# DM3370_LCD_LEDring.net
KiCad netlist of a schematic drawn in Altium Designer
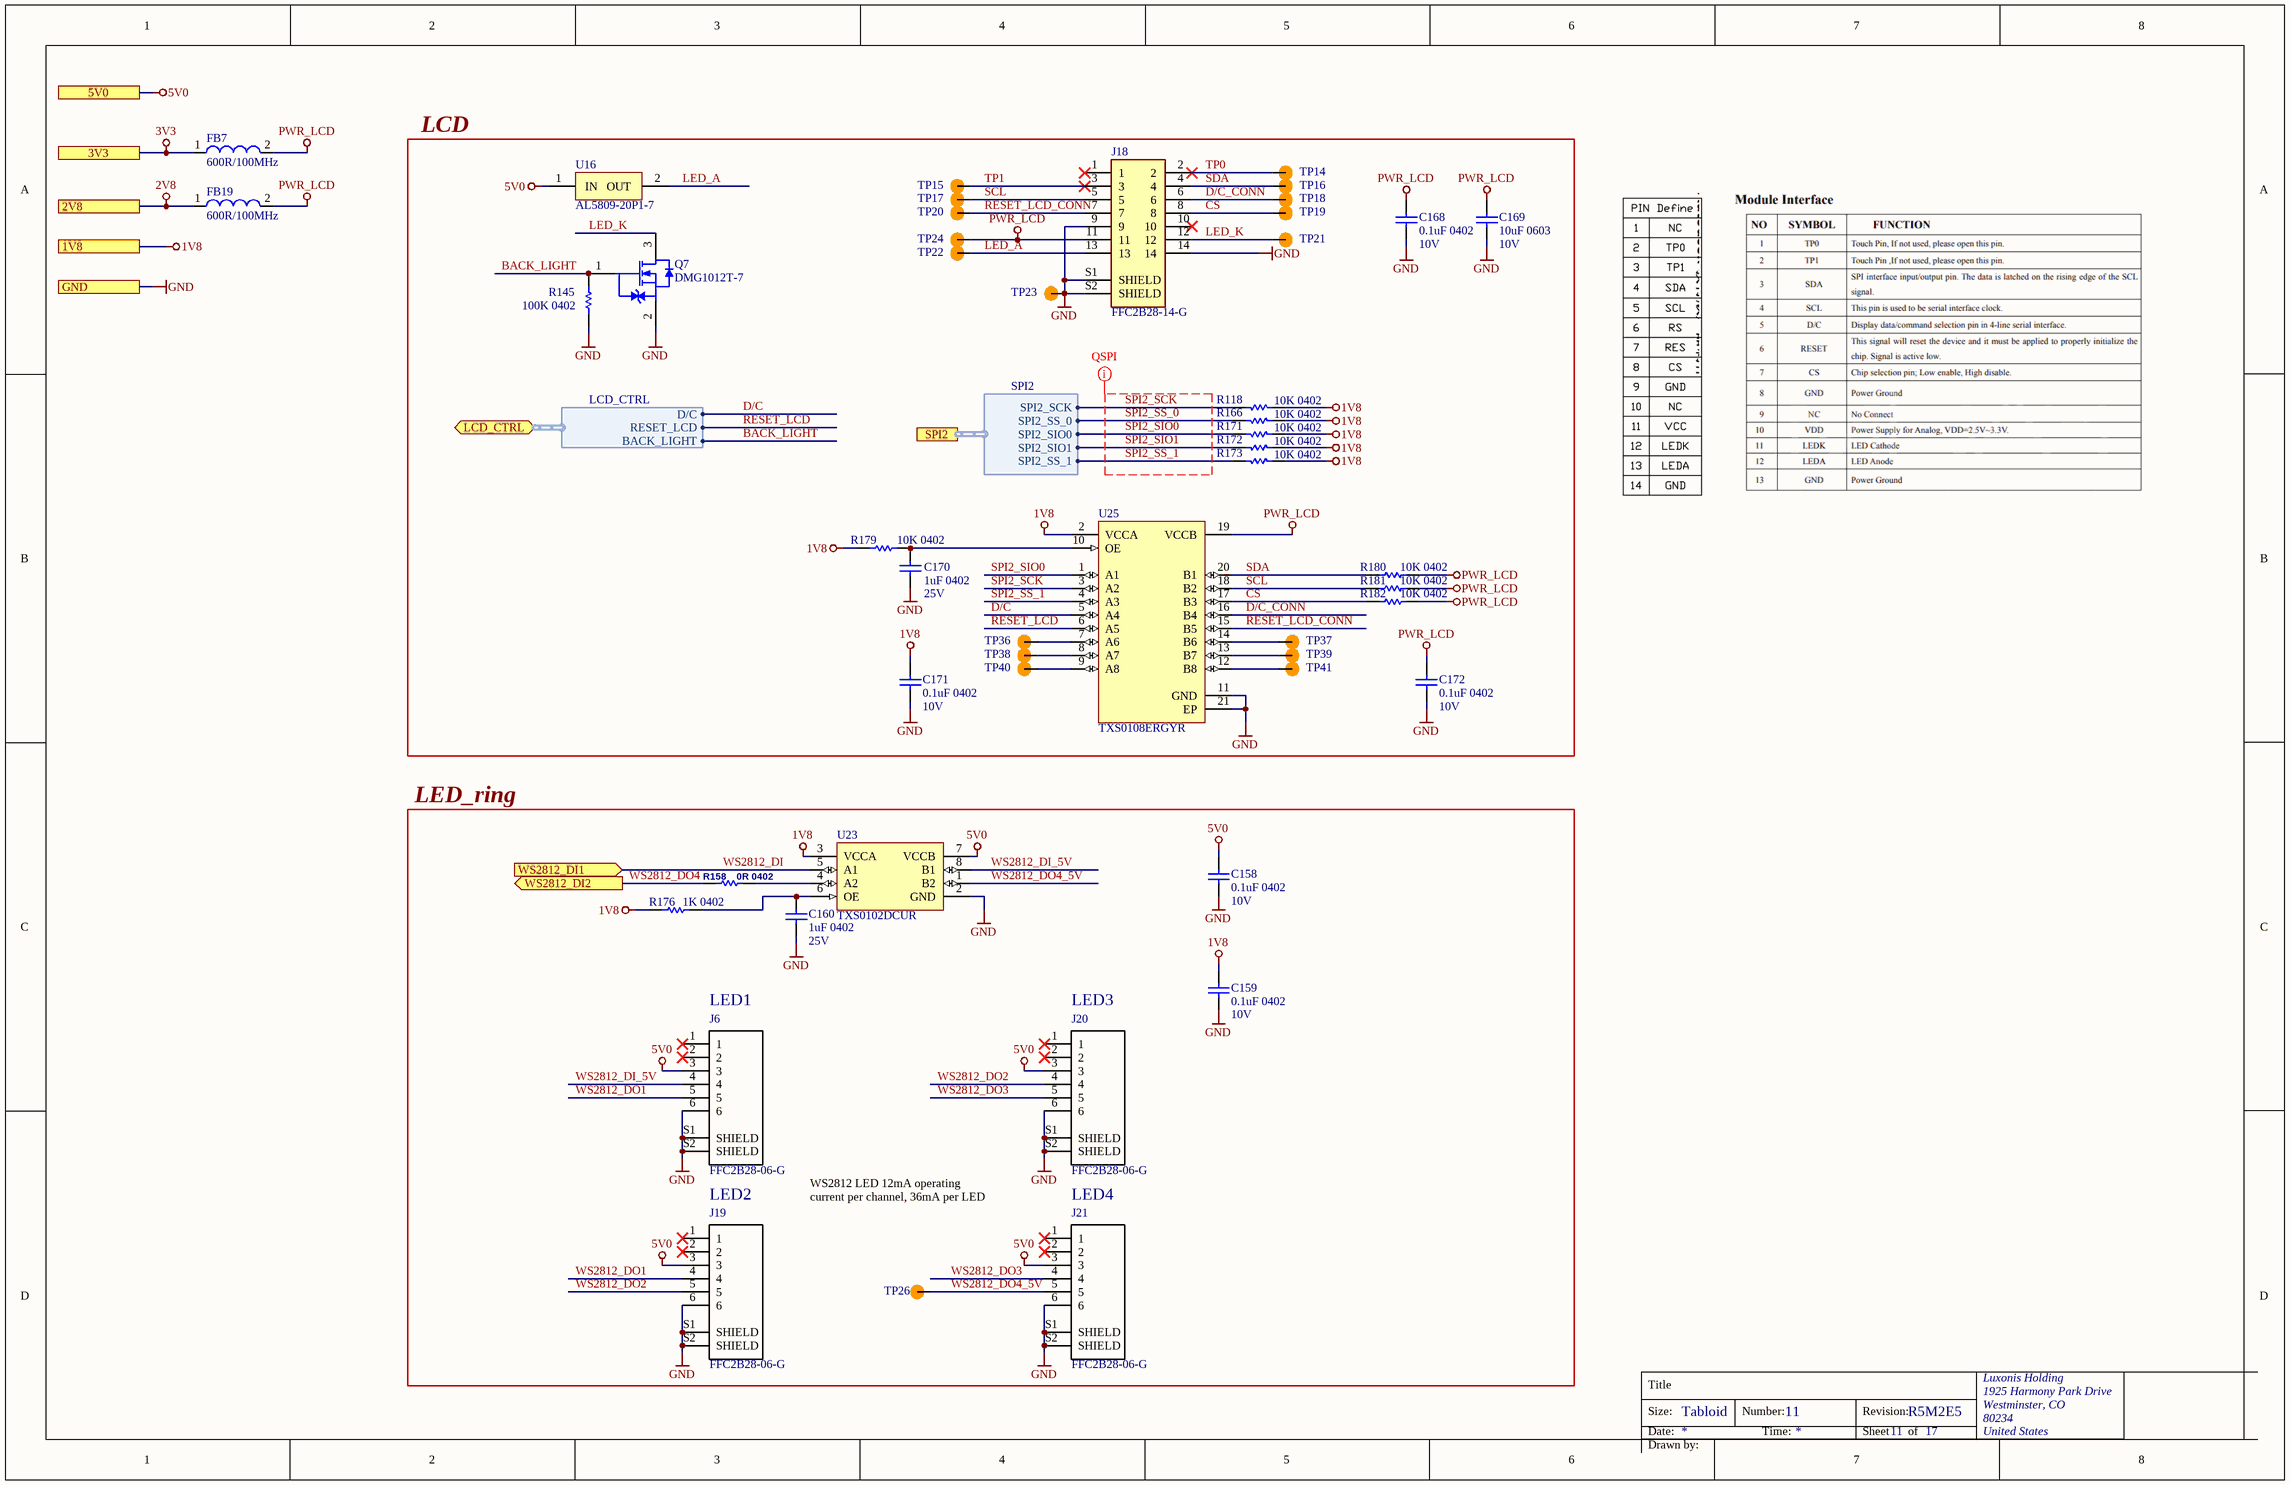
[diagram p0: DM3370_LCD_LEDring.SchDoc]

(export (version "E")
  (design (tool "Eeschema 10.0.6"))
  (components
    (comp (ref "C158")
      (value "0.1uF 0402")
      (footprint "CAP_Altium_Vault_Generic:CAPC0402(1005)70_L")
      (description "CAP CER 0.1UF 10V X7R 0402 5%")
      (fields (field (name "TOLERANCE") "5%") (field (name "VOLTAGE RATING") "10V"))
      (libsource (lib "LuxonisMaster") (part "GRM155R71A104JA01D"))
    )
    (comp (ref "C159")
      (value "0.1uF 0402")
      (footprint "CAP_Altium_Vault_Generic:CAPC0402(1005)70_L")
      (description "CAP CER 0.1UF 10V X7R 0402 5%")
      (fields (field (name "TOLERANCE") "5%") (field (name "VOLTAGE RATING") "10V"))
      (libsource (lib "LuxonisMaster") (part "GRM155R71A104JA01D"))
    )
    (comp (ref "C160")
      (value "1uF 0402")
      (footprint "CAP_Altium_Vault_Generic:CAPC0402(1005)70_L")
      (description "CAP CER 1UF 25V X5R 0402 10%")
      (fields
        (field (name "TOLERANCE") "10%")
        (field (name "VOLTAGE") "25V")
        (field (name "VOLTAGE RATING") "25V")
      )
      (libsource (lib "LuxonisMaster") (part "GRM155R61E105KA12D"))
    )
    (comp (ref "C168")
      (value "0.1uF 0402")
      (footprint "CAP_Altium_Vault_Generic:CAPC0402(1005)70_L")
      (description "CAP CER 0.1UF 10V X7R 0402 5%")
      (fields (field (name "TOLERANCE") "5%") (field (name "VOLTAGE RATING") "10V"))
      (libsource (lib "LuxonisMaster") (part "GRM155R71A104JA01D"))
    )
    (comp (ref "C169")
      (value "10uF 0603")
      (footprint "CAP_Altium_Vault_Generic:CAPC0603(1608)100_L")
      (description "CAP CER 10UF 10V X5R 0603 20%")
      (fields (field (name "TOLERANCE") "20%") (field (name "VOLTAGE RATING") "10V"))
      (libsource (lib "LuxonisMaster") (part "GRM188R61A106ME69D"))
    )
    (comp (ref "C170")
      (value "1uF 0402")
      (footprint "CAP_Altium_Vault_Generic:CAPC0402(1005)70_L")
      (description "CAP CER 1UF 25V X5R 0402 10%")
      (fields
        (field (name "TOLERANCE") "10%")
        (field (name "VOLTAGE") "25V")
        (field (name "VOLTAGE RATING") "25V")
      )
      (libsource (lib "LuxonisMaster") (part "GRM155R61E105KA12D"))
    )
    (comp (ref "C171")
      (value "0.1uF 0402")
      (footprint "CAP_Altium_Vault_Generic:CAPC0402(1005)70_L")
      (description "CAP CER 0.1UF 10V X7R 0402 5%")
      (fields (field (name "TOLERANCE") "5%") (field (name "VOLTAGE RATING") "10V"))
      (libsource (lib "LuxonisMaster") (part "GRM155R71A104JA01D"))
    )
    (comp (ref "C172")
      (value "0.1uF 0402")
      (footprint "CAP_Altium_Vault_Generic:CAPC0402(1005)70_L")
      (description "CAP CER 0.1UF 10V X7R 0402 5%")
      (fields (field (name "TOLERANCE") "5%") (field (name "VOLTAGE RATING") "10V"))
      (libsource (lib "LuxonisMaster") (part "GRM155R71A104JA01D"))
    )
    (comp (ref "FB7")
      (value "600R/100MHz")
      (footprint "LuxonisMaster:2508056017Y2")
      (description "FERRITE BEAD, 0.1OHM, 2A, 0805, 600R/100MHz")
      (fields (field (name "TOLERANCE") "25%"))
      (libsource (lib "LuxonisMaster") (part "2508056017Y2"))
    )
    (comp (ref "FB19")
      (value "600R/100MHz")
      (footprint "LuxonisMaster:2508056017Y2")
      (description "FERRITE BEAD, 0.1OHM, 2A, 0805, 600R/100MHz")
      (fields (field (name "TOLERANCE") "25%"))
      (libsource (lib "LuxonisMaster") (part "2508056017Y2"))
    )
    (comp (ref "J6")
      (value "FFC2B28-06-G")
      (footprint "FFC2B28-06-G")
      (description "Connector, Ffc, R/a Rcpt, 6POS, 1ROW, 0.5MM;")
      (libsource (lib "Luxonis LLC") (part "FFC2B28-06-G"))
    )
    (comp (ref "J18")
      (value "FFC2B28-14-G")
      (footprint "GCT_FFC2B28-14-G")
      (description "14W, 0.5mm FFC Con, R/A, Dual Cont, B/Flp, H1.0mm, Gld, SMT, T&R")
      (libsource (lib "Luxonis LLC") (part "FFC2B28-14-G"))
    )
    (comp (ref "J19")
      (value "FFC2B28-06-G")
      (footprint "FFC2B28-06-G")
      (description "Connector, Ffc, R/a Rcpt, 6POS, 1ROW, 0.5MM;")
      (libsource (lib "Luxonis LLC") (part "FFC2B28-06-G"))
    )
    (comp (ref "J20")
      (value "FFC2B28-06-G")
      (footprint "FFC2B28-06-G")
      (description "Connector, Ffc, R/a Rcpt, 6POS, 1ROW, 0.5MM;")
      (libsource (lib "Luxonis LLC") (part "FFC2B28-06-G"))
    )
    (comp (ref "J21")
      (value "FFC2B28-06-G")
      (footprint "FFC2B28-06-G")
      (description "Connector, Ffc, R/a Rcpt, 6POS, 1ROW, 0.5MM;")
      (libsource (lib "Luxonis LLC") (part "FFC2B28-06-G"))
    )
    (comp (ref "Q7")
      (value "DMG1012T-7")
      (footprint "DMG1012T-7")
      (description "MOSFET N-CH 20V 630MA SOT-523")
      (libsource (lib "Luxonis LLC") (part "DMG1012T-7"))
    )
    (comp (ref "R118")
      (value "10K 0402")
      (footprint "RES_Altium_Vault_Generic:RESC0402(1005)_L")
      (fields (field (name "TOLERANCE") "1%"))
      (libsource (lib "LuxonisMaster") (part "RC0402FR-1310KL"))
    )
    (comp (ref "R145")
      (value "100K 0402")
      (footprint "RES_Altium_Vault_Generic:RESC0402(1005)_L")
      (description "RES SMD 100K OHM 1% 1/16W 0402")
      (fields (field (name "TOLERANCE") "1%"))
      (libsource (lib "LuxonisMaster") (part "RC0402FR-07100KL"))
    )
    (comp (ref "R158")
      (value "0R 0402")
      (footprint "RES_Altium_Vault_Generic:RESC0402(1005)_L")
      (description "RES SMD 0 OHM JUMPER 1/16W 0402")
      (fields (field (name "TOLERANCE") "5%"))
      (libsource (lib "LuxonisMaster") (part "CRCW04020000Z0ED"))
    )
    (comp (ref "R166")
      (value "10K 0402")
      (footprint "RES_Altium_Vault_Generic:RESC0402(1005)_L")
      (fields (field (name "TOLERANCE") "1%"))
      (libsource (lib "LuxonisMaster") (part "RC0402FR-1310KL"))
    )
    (comp (ref "R171")
      (value "10K 0402")
      (footprint "RES_Altium_Vault_Generic:RESC0402(1005)_L")
      (fields (field (name "TOLERANCE") "1%"))
      (libsource (lib "LuxonisMaster") (part "RC0402FR-1310KL"))
    )
    (comp (ref "R172")
      (value "10K 0402")
      (footprint "RES_Altium_Vault_Generic:RESC0402(1005)_L")
      (fields (field (name "TOLERANCE") "1%"))
      (libsource (lib "LuxonisMaster") (part "RC0402FR-1310KL"))
    )
    (comp (ref "R173")
      (value "10K 0402")
      (footprint "RES_Altium_Vault_Generic:RESC0402(1005)_L")
      (fields (field (name "TOLERANCE") "1%"))
      (libsource (lib "LuxonisMaster") (part "RC0402FR-1310KL"))
    )
    (comp (ref "R176")
      (value "1K 0402")
      (footprint "RES_Altium_Vault_Generic:RESC0402(1005)_L")
      (fields (field (name "TOLERANCE") "1%"))
      (libsource (lib "LuxonisMaster") (part "RC0402FR-071KL"))
    )
    (comp (ref "R179")
      (value "10K 0402")
      (footprint "RES_Altium_Vault_Generic:RESC0402(1005)_L")
      (fields (field (name "TOLERANCE") "1%"))
      (libsource (lib "LuxonisMaster") (part "RC0402FR-1310KL"))
    )
    (comp (ref "R180")
      (value "10K 0402")
      (footprint "RES_Altium_Vault_Generic:RESC0402(1005)_L")
      (fields (field (name "TOLERANCE") "1%"))
      (libsource (lib "LuxonisMaster") (part "RC0402FR-1310KL"))
    )
    (comp (ref "R181")
      (value "10K 0402")
      (footprint "RES_Altium_Vault_Generic:RESC0402(1005)_L")
      (fields (field (name "TOLERANCE") "1%"))
      (libsource (lib "LuxonisMaster") (part "RC0402FR-1310KL"))
    )
    (comp (ref "R182")
      (value "10K 0402")
      (footprint "RES_Altium_Vault_Generic:RESC0402(1005)_L")
      (fields (field (name "TOLERANCE") "1%"))
      (libsource (lib "LuxonisMaster") (part "RC0402FR-1310KL"))
    )
    (comp (ref "TP14")
      (value "TEST_POINT")
      (footprint "TP075_150_NS")
      (libsource (lib "Luxonis LLC") (part "TEST_POINT"))
    )
    (comp (ref "TP15")
      (value "TEST_POINT")
      (footprint "TP075_150_NS")
      (libsource (lib "Luxonis LLC") (part "TEST_POINT"))
    )
    (comp (ref "TP16")
      (value "TEST_POINT")
      (footprint "TP075_150_NS")
      (libsource (lib "Luxonis LLC") (part "TEST_POINT"))
    )
    (comp (ref "TP17")
      (value "TEST_POINT")
      (footprint "TP075_150_NS")
      (libsource (lib "Luxonis LLC") (part "TEST_POINT"))
    )
    (comp (ref "TP18")
      (value "TEST_POINT")
      (footprint "TP075_150_NS")
      (libsource (lib "Luxonis LLC") (part "TEST_POINT"))
    )
    (comp (ref "TP19")
      (value "TEST_POINT")
      (footprint "TP075_150_NS")
      (libsource (lib "Luxonis LLC") (part "TEST_POINT"))
    )
    (comp (ref "TP20")
      (value "TEST_POINT")
      (footprint "TP075_150_NS")
      (libsource (lib "Luxonis LLC") (part "TEST_POINT"))
    )
    (comp (ref "TP21")
      (value "TEST_POINT")
      (footprint "TP075_150_NS")
      (libsource (lib "Luxonis LLC") (part "TEST_POINT"))
    )
    (comp (ref "TP22")
      (value "TEST_POINT")
      (footprint "TP075_150_NS")
      (libsource (lib "Luxonis LLC") (part "TEST_POINT"))
    )
    (comp (ref "TP23")
      (value "TEST_POINT")
      (footprint "TP075_150_NS")
      (libsource (lib "Luxonis LLC") (part "TEST_POINT"))
    )
    (comp (ref "TP24")
      (value "TEST_POINT")
      (footprint "TP075_150_NS")
      (libsource (lib "Luxonis LLC") (part "TEST_POINT"))
    )
    (comp (ref "TP26")
      (value "TEST_POINT")
      (footprint "TP075_150_NS")
      (libsource (lib "Luxonis LLC") (part "TEST_POINT"))
    )
    (comp (ref "TP36")
      (value "TEST_POINT")
      (footprint "TP075_150_NS")
      (libsource (lib "Luxonis LLC") (part "TEST_POINT"))
    )
    (comp (ref "TP37")
      (value "TEST_POINT")
      (footprint "TP075_150_NS")
      (libsource (lib "Luxonis LLC") (part "TEST_POINT"))
    )
    (comp (ref "TP38")
      (value "TEST_POINT")
      (footprint "TP075_150_NS")
      (libsource (lib "Luxonis LLC") (part "TEST_POINT"))
    )
    (comp (ref "TP39")
      (value "TEST_POINT")
      (footprint "TP075_150_NS")
      (libsource (lib "Luxonis LLC") (part "TEST_POINT"))
    )
    (comp (ref "TP40")
      (value "TEST_POINT")
      (footprint "TP075_150_NS")
      (libsource (lib "Luxonis LLC") (part "TEST_POINT"))
    )
    (comp (ref "TP41")
      (value "TEST_POINT")
      (footprint "TP075_150_NS")
      (libsource (lib "Luxonis LLC") (part "TEST_POINT"))
    )
    (comp (ref "U16")
      (value "AL5809-20P1-7")
      (footprint "DIOD-POWERDI123-2_B_V")
      (description "Two Terminal Constant Current LED Driver PowerDI, 2.5V to 60V, -40 °C to 125 °C")
      (libsource (lib "Luxonis LLC") (part "DIOD-AL5809-2"))
    )
    (comp (ref "U23")
      (value "TXS0102DCUR")
      (footprint "TXS0102DCUR")
      (description "TEXAS INSTRUMENTS - TXS0102DCUR - IC, TRANSLATOR, 2 BIT, BI, US-8")
      (libsource (lib "Luxonis LLC") (part "TXS0102DCUR"))
    )
    (comp (ref "U25")
      (value "TXS0108ERGYR")
      (footprint "TXS0108ERGYR")
      (description "IC TRNSLTR BIDIRECTIONAL 20VQFN")
      (libsource (lib "Luxonis LLC") (part "TXS0108ERGYR"))
    )
  )
  (nets
    (net (code "3") (name "/BACK_LIGHT") (class "Default")
      (node (ref "Q7") (pin "1") (pinfunction "1_1") (pintype "passive"))
      (node (ref "R145") (pin "2") (pinfunction "2_2") (pintype "passive"))
    )
    (net (code "4") (name "/CS") (class "Default")
      (node (ref "J18") (pin "8") (pinfunction "8_8") (pintype "passive"))
      (node (ref "R182") (pin "1") (pinfunction "1_1") (pintype "passive"))
      (node (ref "TP19") (pin "1") (pintype "passive"))
      (node (ref "U25") (pin "17") (pinfunction "B3_17") (pintype "bidirectional"))
    )
    (net (code "5") (name "/D{slash}C") (class "Default")
      (node (ref "U25") (pin "5") (pinfunction "A4_5") (pintype "bidirectional"))
    )
    (net (code "6") (name "/D{slash}C_CONN") (class "Default")
      (node (ref "J18") (pin "6") (pinfunction "6_6") (pintype "passive"))
      (node (ref "TP18") (pin "1") (pintype "passive"))
      (node (ref "U25") (pin "16") (pinfunction "B4_16") (pintype "bidirectional"))
    )
    (net (code "7") (name "/LED_A") (class "Default")
      (node (ref "J18") (pin "13") (pinfunction "13_13") (pintype "passive"))
      (node (ref "TP22") (pin "1") (pintype "passive"))
      (node (ref "U16") (pin "2") (pinfunction "OUT_2") (pintype "passive"))
    )
    (net (code "8") (name "/LED_K") (class "Default")
      (node (ref "J18") (pin "12") (pinfunction "12_12") (pintype "passive"))
      (node (ref "Q7") (pin "3") (pinfunction "3_3") (pintype "passive"))
      (node (ref "TP21") (pin "1") (pintype "passive"))
    )
    (net (code "9") (name "/RESET_LCD") (class "Default")
      (node (ref "U25") (pin "6") (pinfunction "A5_6") (pintype "bidirectional"))
    )
    (net (code "10") (name "/RESET_LCD_CONN") (class "Default")
      (node (ref "J18") (pin "7") (pinfunction "7_7") (pintype "passive"))
      (node (ref "TP20") (pin "1") (pintype "passive"))
      (node (ref "U25") (pin "15") (pinfunction "B5_15") (pintype "bidirectional"))
    )
    (net (code "11") (name "/SCL") (class "Default")
      (node (ref "J18") (pin "5") (pinfunction "5_5") (pintype "passive"))
      (node (ref "R181") (pin "1") (pinfunction "1_1") (pintype "passive"))
      (node (ref "TP17") (pin "1") (pintype "passive"))
      (node (ref "U25") (pin "18") (pinfunction "B2_18") (pintype "bidirectional"))
    )
    (net (code "12") (name "/SDA") (class "Default")
      (node (ref "J18") (pin "4") (pinfunction "4_4") (pintype "passive"))
      (node (ref "R180") (pin "1") (pinfunction "1_1") (pintype "passive"))
      (node (ref "TP16") (pin "1") (pintype "passive"))
      (node (ref "U25") (pin "20") (pinfunction "B1_20") (pintype "bidirectional"))
    )
    (net (code "13") (name "/SPI2_SCK") (class "Default")
      (node (ref "R118") (pin "2") (pinfunction "2_2") (pintype "passive"))
      (node (ref "U25") (pin "3") (pinfunction "A2_3") (pintype "bidirectional"))
    )
    (net (code "14") (name "/SPI2_SIO0") (class "Default")
      (node (ref "R171") (pin "2") (pinfunction "2_2") (pintype "passive"))
      (node (ref "U25") (pin "1") (pinfunction "A1_1") (pintype "bidirectional"))
    )
    (net (code "15") (name "/SPI2_SIO1") (class "Default")
      (node (ref "R172") (pin "2") (pinfunction "2_2") (pintype "passive"))
    )
    (net (code "16") (name "/SPI2_SS_0") (class "Default")
      (node (ref "R166") (pin "2") (pinfunction "2_2") (pintype "passive"))
    )
    (net (code "17") (name "/SPI2_SS_1") (class "Default")
      (node (ref "R173") (pin "2") (pinfunction "2_2") (pintype "passive"))
      (node (ref "U25") (pin "4") (pinfunction "A3_4") (pintype "bidirectional"))
    )
    (net (code "18") (name "/TP0") (class "Default")
      (node (ref "J18") (pin "2") (pinfunction "2_2") (pintype "passive"))
      (node (ref "TP14") (pin "1") (pintype "passive"))
    )
    (net (code "19") (name "/TP1") (class "Default")
      (node (ref "J18") (pin "3") (pinfunction "3_3") (pintype "passive"))
      (node (ref "TP15") (pin "1") (pintype "passive"))
    )
    (net (code "20") (name "/WS2812_DI") (class "Default")
      (node (ref "U23") (pin "5") (pinfunction "A1_5") (pintype "bidirectional"))
    )
    (net (code "21") (name "/WS2812_DI_5V") (class "Default")
      (node (ref "J6") (pin "4") (pinfunction "4_4") (pintype "passive"))
      (node (ref "U23") (pin "8") (pinfunction "B1_8") (pintype "bidirectional"))
    )
    (net (code "22") (name "/WS2812_DO1") (class "Default")
      (node (ref "J19") (pin "4") (pinfunction "4_4") (pintype "passive"))
      (node (ref "J6") (pin "5") (pinfunction "5_5") (pintype "passive"))
    )
    (net (code "23") (name "/WS2812_DO2") (class "Default")
      (node (ref "J19") (pin "5") (pinfunction "5_5") (pintype "passive"))
      (node (ref "J20") (pin "4") (pinfunction "4_4") (pintype "passive"))
    )
    (net (code "24") (name "/WS2812_DO3") (class "Default")
      (node (ref "J20") (pin "5") (pinfunction "5_5") (pintype "passive"))
      (node (ref "J21") (pin "4") (pinfunction "4_4") (pintype "passive"))
    )
    (net (code "25") (name "/WS2812_DO4") (class "Default")
      (node (ref "R158") (pin "2") (pinfunction "2_2") (pintype "passive"))
    )
    (net (code "26") (name "/WS2812_DO4_5V") (class "Default")
      (node (ref "J21") (pin "5") (pinfunction "5_5") (pintype "passive"))
      (node (ref "TP26") (pin "1") (pintype "passive"))
      (node (ref "U23") (pin "1") (pinfunction "B2_1") (pintype "bidirectional"))
    )
    (net (code "29") (name "1V8") (class "Default")
      (node (ref "C159") (pin "2") (pinfunction "2_2") (pintype "passive"))
      (node (ref "C171") (pin "2") (pinfunction "2_2") (pintype "passive"))
      (node (ref "R118") (pin "1") (pinfunction "1_1") (pintype "passive"))
      (node (ref "R166") (pin "1") (pinfunction "1_1") (pintype "passive"))
      (node (ref "R171") (pin "1") (pinfunction "1_1") (pintype "passive"))
      (node (ref "R172") (pin "1") (pinfunction "1_1") (pintype "passive"))
      (node (ref "R173") (pin "1") (pinfunction "1_1") (pintype "passive"))
      (node (ref "R176") (pin "2") (pinfunction "2_2") (pintype "passive"))
      (node (ref "R179") (pin "2") (pinfunction "2_2") (pintype "passive"))
      (node (ref "U23") (pin "3") (pinfunction "VCCA_3") (pintype "power_in"))
      (node (ref "U25") (pin "2") (pinfunction "VCCA_2") (pintype "power_in"))
    )
    (net (code "30") (name "2V8") (class "Default")
      (node (ref "FB19") (pin "1") (pinfunction "1_1") (pintype "passive"))
    )
    (net (code "31") (name "3V3") (class "Default")
      (node (ref "FB7") (pin "1") (pinfunction "1_1") (pintype "passive"))
    )
    (net (code "32") (name "5V0") (class "Default")
      (node (ref "C158") (pin "2") (pinfunction "2_2") (pintype "passive"))
      (node (ref "J19") (pin "3") (pinfunction "3_3") (pintype "passive"))
      (node (ref "J20") (pin "3") (pinfunction "3_3") (pintype "passive"))
      (node (ref "J21") (pin "3") (pinfunction "3_3") (pintype "passive"))
      (node (ref "J6") (pin "3") (pinfunction "3_3") (pintype "passive"))
      (node (ref "U16") (pin "1") (pinfunction "IN_1") (pintype "passive"))
      (node (ref "U23") (pin "7") (pinfunction "VCCB_7") (pintype "power_in"))
    )
    (net (code "33") (name "GND") (class "Default")
      (node (ref "C158") (pin "1") (pinfunction "1_1") (pintype "passive"))
      (node (ref "C159") (pin "1") (pinfunction "1_1") (pintype "passive"))
      (node (ref "C160") (pin "1") (pinfunction "1_1") (pintype "passive"))
      (node (ref "C168") (pin "1") (pinfunction "1_1") (pintype "passive"))
      (node (ref "C169") (pin "1") (pinfunction "1_1") (pintype "passive"))
      (node (ref "C170") (pin "1") (pinfunction "1_1") (pintype "passive"))
      (node (ref "C171") (pin "1") (pinfunction "1_1") (pintype "passive"))
      (node (ref "C172") (pin "1") (pinfunction "1_1") (pintype "passive"))
      (node (ref "J18") (pin "14") (pinfunction "14_14") (pintype "passive"))
      (node (ref "J18") (pin "9") (pinfunction "9_9") (pintype "passive"))
      (node (ref "J18") (pin "S1") (pinfunction "SHIELD_S1") (pintype "passive"))
      (node (ref "J18") (pin "S2") (pinfunction "SHIELD_S2") (pintype "passive"))
      (node (ref "J19") (pin "6") (pinfunction "6_6") (pintype "passive"))
      (node (ref "J19") (pin "S1") (pinfunction "SHIELD_S1") (pintype "passive"))
      (node (ref "J19") (pin "S2") (pinfunction "SHIELD_S2") (pintype "passive"))
      (node (ref "J20") (pin "6") (pinfunction "6_6") (pintype "passive"))
      (node (ref "J20") (pin "S1") (pinfunction "SHIELD_S1") (pintype "passive"))
      (node (ref "J20") (pin "S2") (pinfunction "SHIELD_S2") (pintype "passive"))
      (node (ref "J21") (pin "6") (pinfunction "6_6") (pintype "passive"))
      (node (ref "J21") (pin "S1") (pinfunction "SHIELD_S1") (pintype "passive"))
      (node (ref "J21") (pin "S2") (pinfunction "SHIELD_S2") (pintype "passive"))
      (node (ref "J6") (pin "6") (pinfunction "6_6") (pintype "passive"))
      (node (ref "J6") (pin "S1") (pinfunction "SHIELD_S1") (pintype "passive"))
      (node (ref "J6") (pin "S2") (pinfunction "SHIELD_S2") (pintype "passive"))
      (node (ref "Q7") (pin "2") (pinfunction "2_2") (pintype "passive"))
      (node (ref "R145") (pin "1") (pinfunction "1_1") (pintype "passive"))
      (node (ref "TP23") (pin "1") (pintype "passive"))
      (node (ref "U23") (pin "2") (pinfunction "GND_2") (pintype "power_in"))
      (node (ref "U25") (pin "11") (pinfunction "GND_11") (pintype "power_in"))
      (node (ref "U25") (pin "21") (pinfunction "EP_21") (pintype "power_in"))
    )
    (net (code "34") (name "Net-(U23-A2)") (class "Default")
      (node (ref "R158") (pin "1") (pinfunction "1_1") (pintype "passive"))
      (node (ref "U23") (pin "4") (pinfunction "A2_4") (pintype "bidirectional"))
    )
    (net (code "35") (name "Net-(U23-OE)") (class "Default")
      (node (ref "C160") (pin "2") (pinfunction "2_2") (pintype "passive"))
      (node (ref "R176") (pin "1") (pinfunction "1_1") (pintype "passive"))
      (node (ref "U23") (pin "6") (pinfunction "OE_6") (pintype "input"))
    )
    (net (code "36") (name "Net-(U25-A6)") (class "Default")
      (node (ref "TP36") (pin "1") (pintype "passive"))
      (node (ref "U25") (pin "7") (pinfunction "A6_7") (pintype "bidirectional"))
    )
    (net (code "37") (name "Net-(U25-A7)") (class "Default")
      (node (ref "TP38") (pin "1") (pintype "passive"))
      (node (ref "U25") (pin "8") (pinfunction "A7_8") (pintype "bidirectional"))
    )
    (net (code "38") (name "Net-(U25-A8)") (class "Default")
      (node (ref "TP40") (pin "1") (pintype "passive"))
      (node (ref "U25") (pin "9") (pinfunction "A8_9") (pintype "bidirectional"))
    )
    (net (code "39") (name "Net-(U25-B6)") (class "Default")
      (node (ref "TP37") (pin "1") (pintype "passive"))
      (node (ref "U25") (pin "14") (pinfunction "B6_14") (pintype "bidirectional"))
    )
    (net (code "40") (name "Net-(U25-B7)") (class "Default")
      (node (ref "TP39") (pin "1") (pintype "passive"))
      (node (ref "U25") (pin "13") (pinfunction "B7_13") (pintype "bidirectional"))
    )
    (net (code "41") (name "Net-(U25-B8)") (class "Default")
      (node (ref "TP41") (pin "1") (pintype "passive"))
      (node (ref "U25") (pin "12") (pinfunction "B8_12") (pintype "bidirectional"))
    )
    (net (code "42") (name "Net-(U25-OE)") (class "Default")
      (node (ref "C170") (pin "2") (pinfunction "2_2") (pintype "passive"))
      (node (ref "R179") (pin "1") (pinfunction "1_1") (pintype "passive"))
      (node (ref "U25") (pin "10") (pinfunction "OE_10") (pintype "input"))
    )
    (net (code "43") (name "PWR_LCD") (class "Default")
      (node (ref "C168") (pin "2") (pinfunction "2_2") (pintype "passive"))
      (node (ref "C169") (pin "2") (pinfunction "2_2") (pintype "passive"))
      (node (ref "C172") (pin "2") (pinfunction "2_2") (pintype "passive"))
      (node (ref "FB19") (pin "2") (pinfunction "2_2") (pintype "passive"))
      (node (ref "FB7") (pin "2") (pinfunction "2_2") (pintype "passive"))
      (node (ref "J18") (pin "11") (pinfunction "11_11") (pintype "passive"))
      (node (ref "R180") (pin "2") (pinfunction "2_2") (pintype "passive"))
      (node (ref "R181") (pin "2") (pinfunction "2_2") (pintype "passive"))
      (node (ref "R182") (pin "2") (pinfunction "2_2") (pintype "passive"))
      (node (ref "TP24") (pin "1") (pintype "passive"))
      (node (ref "U25") (pin "19") (pinfunction "VCCB_19") (pintype "power_in"))
    )
    (net (code "44") (name "unconnected-(J6-Pad1)") (class "Default")
      (node (ref "J6") (pin "1") (pinfunction "1_1") (pintype "passive+no_connect"))
    )
    (net (code "45") (name "unconnected-(J6-Pad2)") (class "Default")
      (node (ref "J6") (pin "2") (pinfunction "2_2") (pintype "passive+no_connect"))
    )
    (net (code "46") (name "unconnected-(J18-Pad1)") (class "Default")
      (node (ref "J18") (pin "1") (pinfunction "1_1") (pintype "passive+no_connect"))
    )
    (net (code "47") (name "unconnected-(J18-Pad10)") (class "Default")
      (node (ref "J18") (pin "10") (pinfunction "10_10") (pintype "passive+no_connect"))
    )
    (net (code "48") (name "unconnected-(J19-Pad1)") (class "Default")
      (node (ref "J19") (pin "1") (pinfunction "1_1") (pintype "passive+no_connect"))
    )
    (net (code "49") (name "unconnected-(J19-Pad2)") (class "Default")
      (node (ref "J19") (pin "2") (pinfunction "2_2") (pintype "passive+no_connect"))
    )
    (net (code "50") (name "unconnected-(J20-Pad1)") (class "Default")
      (node (ref "J20") (pin "1") (pinfunction "1_1") (pintype "passive+no_connect"))
    )
    (net (code "51") (name "unconnected-(J20-Pad2)") (class "Default")
      (node (ref "J20") (pin "2") (pinfunction "2_2") (pintype "passive+no_connect"))
    )
    (net (code "52") (name "unconnected-(J21-Pad1)") (class "Default")
      (node (ref "J21") (pin "1") (pinfunction "1_1") (pintype "passive+no_connect"))
    )
    (net (code "53") (name "unconnected-(J21-Pad2)") (class "Default")
      (node (ref "J21") (pin "2") (pinfunction "2_2") (pintype "passive+no_connect"))
    )
  )
)
